# Ancillaries.net
KiCad netlist of a schematic drawn in Altium Designer
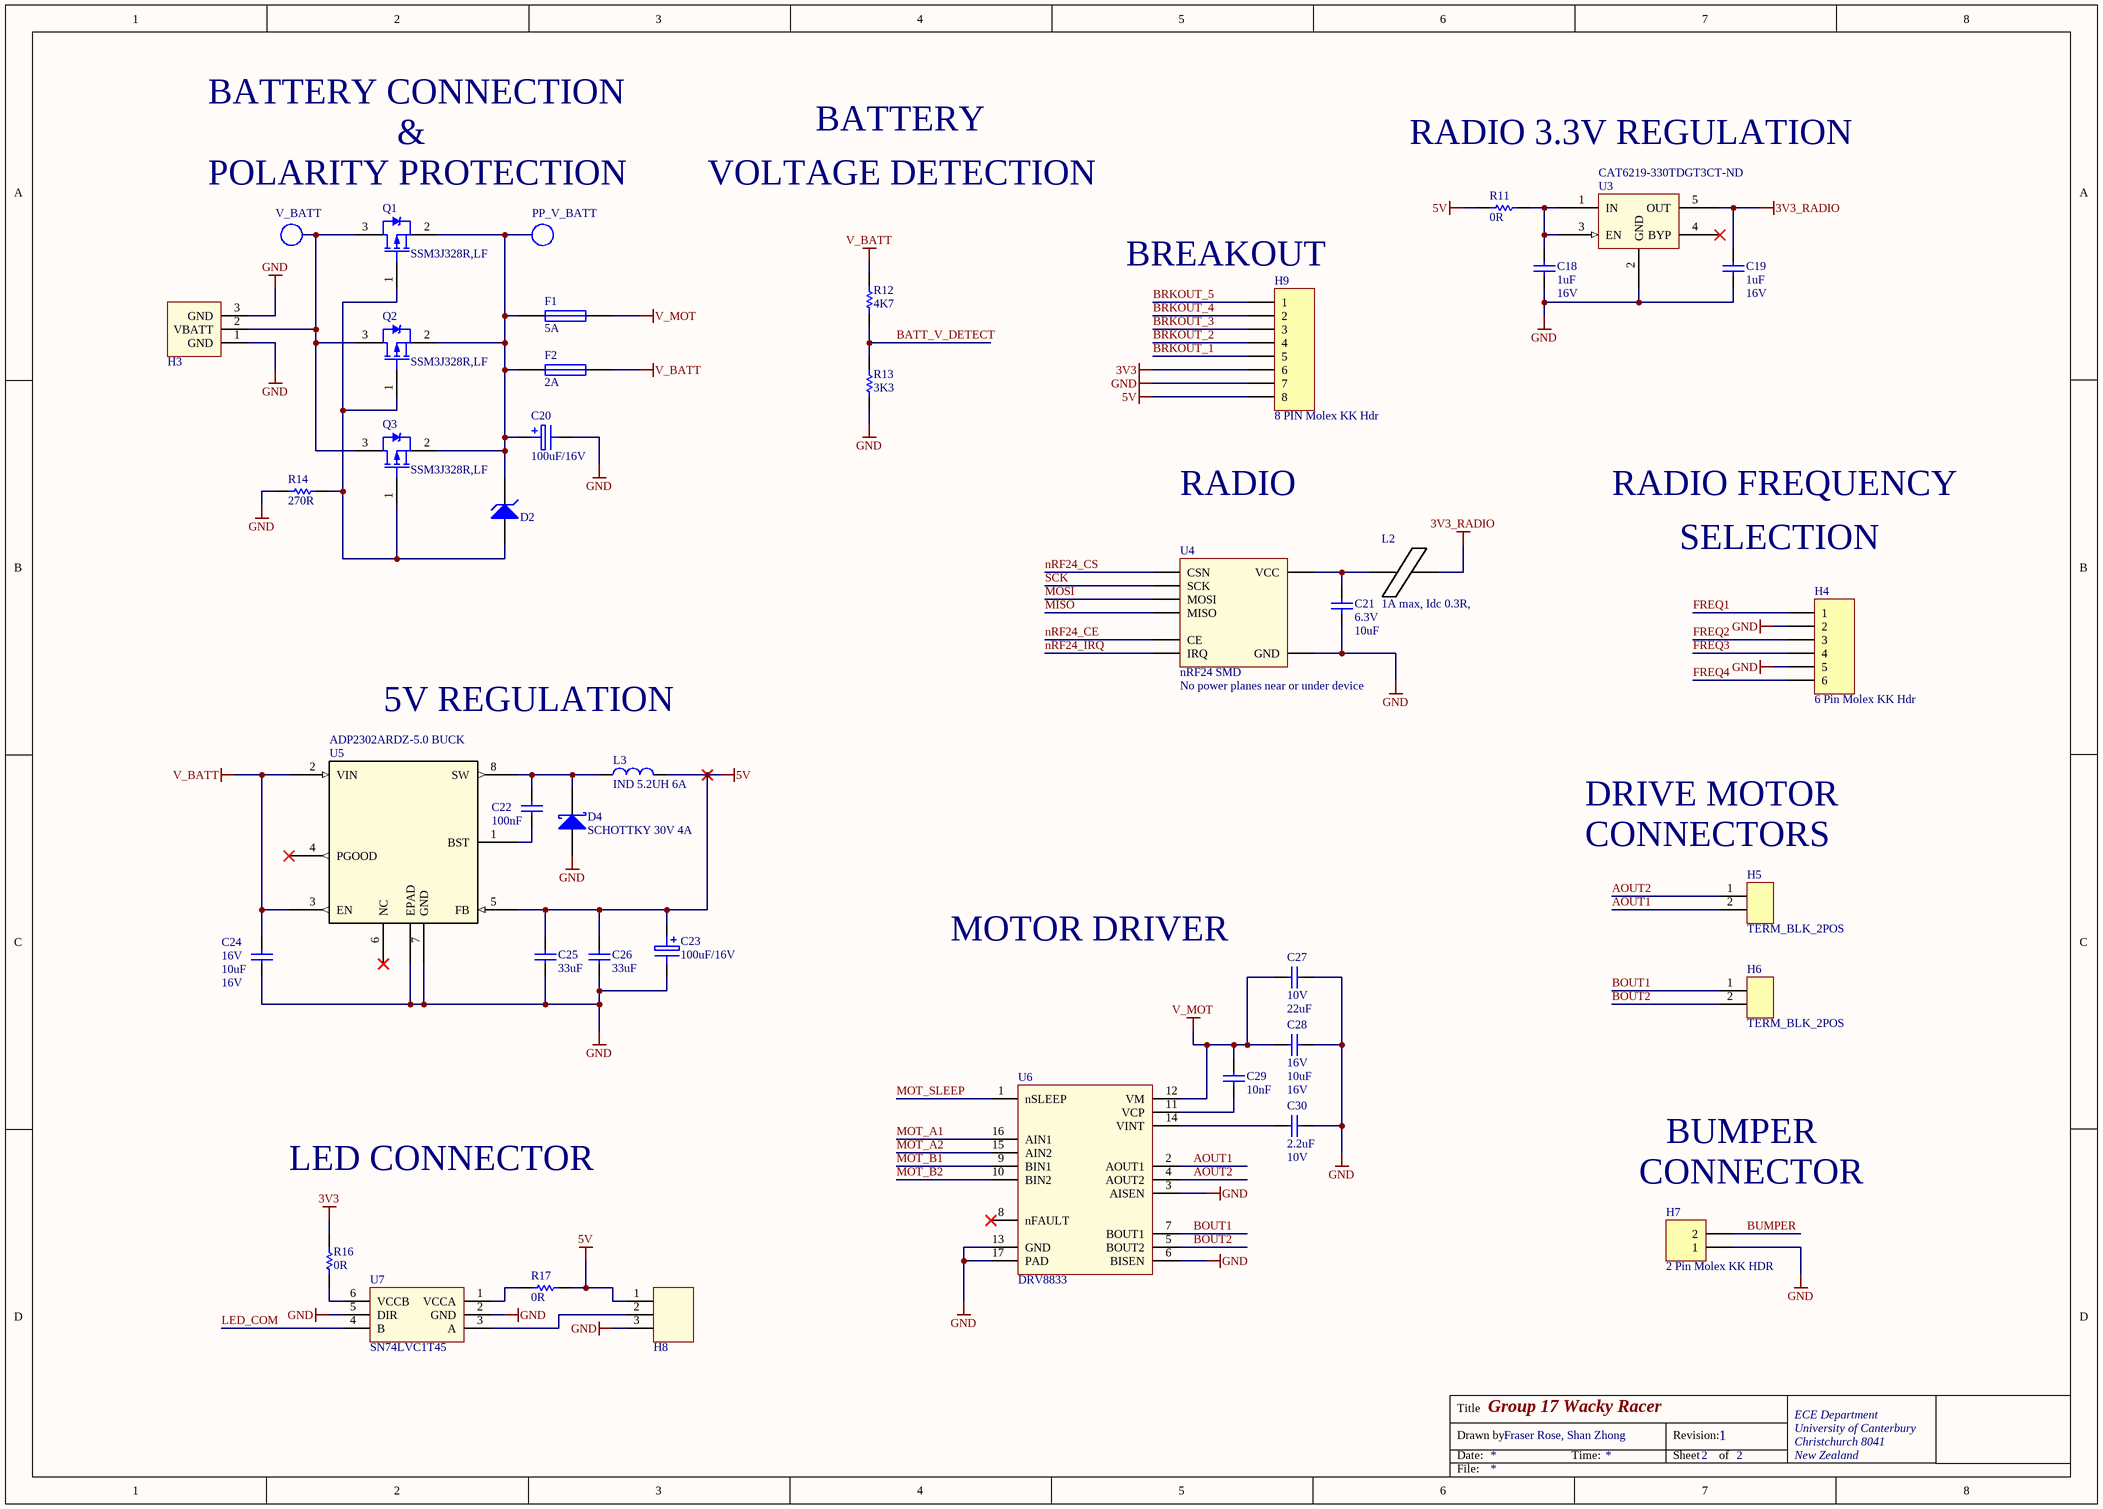
[diagram p0: Ancillaries.SchDoc]

(export (version "E")
  (design (tool "Eeschema 10.0.6"))
  (components
    (comp (ref "1")
      (value "V_BATT")
      (footprint "TP_0603")
      (description "Test Point 1.65X0.9X1.2mm SMD")
      (fields
        (field (name "MANUFACTURER") "TE Connectivity AMP Connectors")
        (field (name "MANUFACTURER PART NUMBER") "1625854-3")
      )
      (libsource (lib "ECE AD19Components_19V1") (part "TP_0603"))
    )
    (comp (ref "2")
      (value "PP_V_BATT")
      (footprint "TP_0603")
      (description "Test Point 1.65X0.9X1.2mm SMD")
      (fields
        (field (name "MANUFACTURER") "TE Connectivity AMP Connectors")
        (field (name "MANUFACTURER PART NUMBER") "1625854-3")
      )
      (libsource (lib "ECE AD19Components_19V1") (part "TP_0603"))
    )
    (comp (ref "C18")
      (value "1uF")
      (footprint "CAPC1608N")
      (description "CAP CER 1uF Y5V -20% +80% 16V 0603")
      (fields (field (name "MAX VOLTAGE") "16V"))
      (libsource (lib "ECE AD19Components_19V1") (part "CC_1uF_0603"))
    )
    (comp (ref "C19")
      (value "1uF")
      (footprint "CAPC1608N")
      (description "CAP CER 1uF Y5V -20% +80% 16V 0603")
      (fields (field (name "MAX VOLTAGE") "16V"))
      (libsource (lib "ECE AD19Components_19V1") (part "CC_1uF_0603"))
    )
    (comp (ref "C20")
      (value "100uF/16V")
      (footprint "NICH-1")
      (description "CAP ALUM 100uF 16V SMD")
      (fields (field (name "MANUFACTURER") "Nichcon"))
      (libsource (lib "ECE AD19Components_19V1") (part "CA_100uF_16V"))
    )
    (comp (ref "C21")
      (value "10uF")
      (footprint "CAPC1608N")
      (description "CAP CER 10UF X5R +-20% 6V3 0603")
      (fields (field (name "VOLTAGE - RATED") "6.3V"))
      (libsource (lib "ECE AD19Components_19V1") (part "CC_10uF_0603"))
    )
    (comp (ref "C22")
      (value "100nF")
      (footprint "CAPC1608N")
      (description "CAP CER 100nF X7R +-10% 50V 0603")
      (libsource (lib "ECE AD19Components_19V1") (part "CC_100nF_0603"))
    )
    (comp (ref "C23")
      (value "100uF/16V")
      (footprint "NICH-1")
      (description "CAP ALUM 100uF 16V SMD")
      (fields (field (name "MANUFACTURER") "Nichcon"))
      (libsource (lib "ECE AD19Components_19V1") (part "CA_100uF_16V"))
    )
    (comp (ref "C24")
      (value "10uF")
      (footprint "CAPC2012N")
      (description "CAP CER 10uF X5R 16V 0805")
      (fields
        (field (name "MANUFACTURER") "Samsung Electro-Mechanics")
        (field (name "MANUFACTURER PART NUMBER") "CL21A106KOQNNWE")
        (field (name "VOLTAGE - RATED") "16V")
        (field (name "MAX VOLTAGE") "16V")
      )
      (libsource (lib "ENCE461AD19_19V2") (part "CC_10uF_16V_0805"))
    )
    (comp (ref "C25")
      (value "33uF")
      (footprint "CAPC2012N")
      (description "CAP CER 33uF X5R 6V3 0805")
      (fields
        (field (name "MANUFACTURER") "TDK Corporation")
        (field (name "MANUFACTURER PART NUMBER") "C2012X5R0J336M125AC")
      )
      (libsource (lib "ENCE461AD19_19V2") (part "CC_33uF_6V3_0805"))
    )
    (comp (ref "C26")
      (value "33uF")
      (footprint "CAPC2012N")
      (description "CAP CER 33uF X5R 6V3 0805")
      (fields
        (field (name "MANUFACTURER") "TDK Corporation")
        (field (name "MANUFACTURER PART NUMBER") "C2012X5R0J336M125AC")
      )
      (libsource (lib "ENCE461AD19_19V2") (part "CC_33uF_6V3_0805"))
    )
    (comp (ref "C27")
      (value "22uF")
      (footprint "CAPC3216N")
      (description "CAP CER 22uF Y5V -20% +80% 10V 1206")
      (fields (field (name "MAX VOLTAGE") "10V"))
      (libsource (lib "ECE AD19Components_19V1") (part "CC_22uF_1206"))
    )
    (comp (ref "C28")
      (value "10uF")
      (footprint "CAPC2012N")
      (description "CAP CER 10uF X5R 16V 0805")
      (fields
        (field (name "MANUFACTURER") "Samsung Electro-Mechanics")
        (field (name "MANUFACTURER PART NUMBER") "CL21A106KOQNNWE")
        (field (name "VOLTAGE - RATED") "16V")
        (field (name "MAX VOLTAGE") "16V")
      )
      (libsource (lib "ENCE461AD19_19V2") (part "CC_10uF_16V_0805"))
    )
    (comp (ref "C29")
      (value "10nF")
      (footprint "CAPC1608N")
      (description "CAP CER 10nF X7R +-10% 50V 0603")
      (libsource (lib "ECE AD19Components_19V1") (part "CC_10nF_0603"))
    )
    (comp (ref "C30")
      (value "2.2uF")
      (footprint "CAPC1608N")
      (description "CAP CER 2.2uF X5R +-20% 10V 0603")
      (fields (field (name "MAX VOLTAGE") "10V"))
      (libsource (lib "ECE AD19Components_19V1") (part "CC_2.2uF_0603"))
    )
    (comp (ref "D2")
      (value "DIODE ZENER 5.6V")
      (footprint "DO-214AA_SCL")
      (description "DIODE ZENER 5.6V 5W DO214AA")
      (fields
        (field (name "MANUFACTURER") "Micro Commercial Co")
        (field (name "MANUFACTURER PART NUMBER") "SMBJ5339B-TP")
      )
      (libsource (lib "ENCE461AD19_19V2") (part "SMBJ5339B-TP"))
    )
    (comp (ref "D4")
      (value "SCHOTTKY 30V 4A")
      (footprint "SMC")
      (description "DIODE SCHOTTKY 30V 4A SMC")
      (fields
        (field (name "MANUFACTURER") "ON Semiconductor")
        (field (name "MANUFACTURER PART NUMBER") "MBRS330T3G")
      )
      (libsource (lib "ENCE461AD19_19V2") (part "MBRS330T3G"))
    )
    (comp (ref "F1")
      (value "5A")
      (footprint "RESC3216N")
      (description "Fuse 5.0A Fast Acting 1206 SMD")
      (fields (field (name "MANUFACTURER PART NUMBER") "C1F5") (field (name "MANUFACTURER") "Bel TRP"))
      (libsource (lib "ECE AD19Components_19V1") (part "FS_Fuse_5.0A"))
    )
    (comp (ref "F2")
      (value "2A")
      (footprint "RESC3216N")
      (description "Fuse 2.0A Very Fast Acting 1206 SMD")
      (fields
        (field (name "MANUFACTURER") "MULTICOMP")
        (field (name "MANUFACTURER PART NUMBER") "MC12CF 002")
      )
      (libsource (lib "ECE AD19Components_19V1") (part "FS_Fuse_2.0A"))
    )
    (comp (ref "H3")
      (value "Battery_HEADER_3pin")
      (footprint "BATT_HEADER_3POS")
      (description "3Pin Header 2.54mm spacing")
      (libsource (lib "ENCE461AD19_19V2") (part "Battery_HEADER_3pin"))
    )
    (comp (ref "H4")
      (value "6 Pin Molex KK Hdr")
      (footprint "MOLEX_KK_6_HDR")
      (description "CONN HEADER 6POS 2.54mm VERT_Thru Hole")
      (libsource (lib "ECE AD19Components_19V1") (part "JA_MOLEX_KK_6POS"))
    )
    (comp (ref "H5")
      (value "TERM_BLK_2POS")
      (footprint "TERM_BLK_2POS")
      (description "2 Position Terminal Block 7.62mm spacing")
      (libsource (lib "ENCE461AD19_19V2") (part "TERM_BLK_2POS"))
    )
    (comp (ref "H6")
      (value "TERM_BLK_2POS")
      (footprint "TERM_BLK_2POS")
      (description "2 Position Terminal Block 7.62mm spacing")
      (libsource (lib "ENCE461AD19_19V2") (part "TERM_BLK_2POS"))
    )
    (comp (ref "H7")
      (value "2 Pin Molex KK HDR")
      (footprint "MOLEX_KK_2_HDR")
      (description "CONN HEADER 2POS 2.54mm VERT_Thru Hole")
      (libsource (lib "ECE AD19Components_19V1") (part "JA_MOLEX_KK_2POS"))
    )
    (comp (ref "H8")
      (value "HEADER_3")
      (footprint "HEADER_3POS")
      (description "3Pin Header 2.54mm spacing")
      (libsource (lib "ENCE461AD19_19V2") (part "HEADER_3"))
    )
    (comp (ref "H9")
      (value "8 PIN Molex KK Hdr")
      (footprint "MOLEX_KK_8_HDR")
      (description "CONN HEADER 8POS 2.54mm VERT_Thru Hole")
      (libsource (lib "ECE AD19Components_19V1") (part "JA_MOLEX_KK_8POS"))
    )
    (comp (ref "L2")
      (value "1A max, Idc 0.3R,")
      (footprint "INDC3216L")
      (description "Ferrite Bead, Rdc 0.3R, Z100MHZ 600R, Imax 1A, SMD 1206")
      (fields
        (field (name "MANUFACTURER") "FAIR-RITE")
        (field (name "MANUFACTURER PART NUMBER") "2512066017Y1")
      )
      (libsource (lib "ECE AD19Components_19V1") (part "IN_Ferrite-Bead"))
    )
    (comp (ref "L3")
      (value "IND 5.2UH 6A")
      (footprint "INDUCTOR5u2")
      (description "FIXED IND 5.2UH 6A 22 MOHM SMD")
      (fields
        (field (name "MANUFACTURER") "Sumida America Components Inc.")
        (field (name "MANUFACTURER PART NUMBER") "CDRH104RNP-5R2NC")
      )
      (libsource (lib "ENCE461AD19_19V2") (part "CDRH104RNP-5R2NC"))
    )
    (comp (ref "Q1")
      (value "SSM3J328R,LF")
      (footprint "SOT23_N")
      (description "MOSFET P-CH 20V 6A SOT23-3")
      (fields
        (field (name "MANUFACTURER") "Toshiba")
        (field (name "MANUFACTURER PART NUMBER") "SSM3J328R,LF")
      )
      (libsource (lib "ECE AD19Components_19V1") (part "TM_SSM3J328R"))
    )
    (comp (ref "Q2")
      (value "SSM3J328R,LF")
      (footprint "SOT23_N")
      (description "MOSFET P-CH 20V 6A SOT23-3")
      (fields
        (field (name "MANUFACTURER") "Toshiba")
        (field (name "MANUFACTURER PART NUMBER") "SSM3J328R,LF")
      )
      (libsource (lib "ECE AD19Components_19V1") (part "TM_SSM3J328R"))
    )
    (comp (ref "Q3")
      (value "SSM3J328R,LF")
      (footprint "SOT23_N")
      (description "MOSFET P-CH 20V 6A SOT23-3")
      (fields
        (field (name "MANUFACTURER") "Toshiba")
        (field (name "MANUFACTURER PART NUMBER") "SSM3J328R,LF")
      )
      (libsource (lib "ECE AD19Components_19V1") (part "TM_SSM3J328R"))
    )
    (comp (ref "R11")
      (value "0R")
      (footprint "RESC1608N")
      (description "RES 0.0 OHM 1/10W 5% 0603 SMD")
      (libsource (lib "ECE AD19Components_19V1") (part "RS_0R0"))
    )
    (comp (ref "R12")
      (value "4K7")
      (footprint "RESC1608N")
      (description "RES 4.7K OHM 1/10W 5% 0603 SMD")
      (libsource (lib "ECE AD19Components_19V1") (part "RS_4K7"))
    )
    (comp (ref "R13")
      (value "3K3")
      (footprint "RESC1608N")
      (description "RES 3.3K OHM 1/10W 5% 0603 SMD")
      (libsource (lib "ECE AD19Components_19V1") (part "RS_3K3"))
    )
    (comp (ref "R14")
      (value "270R")
      (footprint "RESC1608N")
      (description "RES 270 OHM 1/10W 5% 0603 SMD")
      (libsource (lib "ECE AD19Components_19V1") (part "RS_270R"))
    )
    (comp (ref "R16")
      (value "0R")
      (footprint "RESC1608N")
      (description "RES 0.0 OHM 1/10W 5% 0603 SMD")
      (libsource (lib "ECE AD19Components_19V1") (part "RS_0R0"))
    )
    (comp (ref "R17")
      (value "0R")
      (footprint "RESC1608N")
      (description "RES 0.0 OHM 1/10W 5% 0603 SMD")
      (libsource (lib "ECE AD19Components_19V1") (part "RS_0R0"))
    )
    (comp (ref "U3")
      (value "CAT6219-330TDGT3")
      (footprint "SOT95P280X145-5N")
      (description "IC REG LIN 3.3V 500MA TSOT23-5")
      (fields
        (field (name "BASE PART NUMBER") "CAT6219")
        (field (name "SUPPLIER PART NUMBER") "CAT6219-330TDGT3CT-ND")
      )
      (libsource (lib "ENCE461AD19_19V2") (part "SV_CAT6219-330TDGT3"))
    )
    (comp (ref "U4")
      (value "nRF24 SMD")
      (footprint "NRF24")
      (description "nRF24 SMD Module")
      (fields (field (name "WARNING") "No power planes near or under device"))
      (libsource (lib "ENCE461AD19_19V2") (part "NRF24"))
    )
    (comp (ref "U5")
      (value "ADP2302ARDZ-5.0 BUCK")
      (footprint "RD_8_1")
      (description "IC REG BUCK 5V 2A 8SOIC")
      (fields (field (name "MANUFACTURER_PART_NUMBER") "ADP2302ARDZ-5.0-R7"))
      (libsource (lib "ENCE461AD19_19V2") (part "ADP2302ARDZ-5.0-R7"))
    )
    (comp (ref "U6")
      (value "DRV8833")
      (footprint "HTSOP16")
      (description "Dual H-Bridge Motor Driver 1.5A")
      (libsource (lib "ENCE461AD19_19V2") (part "DRV8833"))
    )
    (comp (ref "U7")
      (value "SN74LVC1T45")
      (footprint "SOT23-6_N")
      (description "1.8V - 5V level converter")
      (libsource (lib "ENCE461_extras_2020") (part "SN74LVC1T45"))
    )
  )
  (nets
    (net (code "1") (name "/AOUT1") (class "Default")
      (node (ref "H5") (pin "2") (pintype "passive"))
      (node (ref "U6") (pin "2") (pinfunction "AOUT1_2") (pintype "passive"))
    )
    (net (code "2") (name "/AOUT2") (class "Default")
      (node (ref "H5") (pin "1") (pintype "passive"))
      (node (ref "U6") (pin "4") (pinfunction "AOUT2_4") (pintype "passive"))
    )
    (net (code "3") (name "/BATT_V_DETECT") (class "Default")
      (node (ref "R12") (pin "1") (pinfunction "1_1") (pintype "passive"))
      (node (ref "R13") (pin "2") (pinfunction "2_2") (pintype "passive"))
    )
    (net (code "4") (name "/BOUT1") (class "Default")
      (node (ref "H6") (pin "1") (pintype "passive"))
      (node (ref "U6") (pin "7") (pinfunction "BOUT1_7") (pintype "passive"))
    )
    (net (code "5") (name "/BOUT2") (class "Default")
      (node (ref "H6") (pin "2") (pintype "passive"))
      (node (ref "U6") (pin "5") (pinfunction "BOUT2_5") (pintype "passive"))
    )
    (net (code "6") (name "/BRKOUT_1") (class "Default")
      (node (ref "H9") (pin "5") (pinfunction "5_5") (pintype "passive"))
    )
    (net (code "7") (name "/BRKOUT_2") (class "Default")
      (node (ref "H9") (pin "4") (pinfunction "4_4") (pintype "passive"))
    )
    (net (code "8") (name "/BRKOUT_3") (class "Default")
      (node (ref "H9") (pin "3") (pinfunction "3_3") (pintype "passive"))
    )
    (net (code "9") (name "/BRKOUT_4") (class "Default")
      (node (ref "H9") (pin "2") (pinfunction "2_2") (pintype "passive"))
    )
    (net (code "10") (name "/BRKOUT_5") (class "Default")
      (node (ref "H9") (pin "1") (pinfunction "1_1") (pintype "passive"))
    )
    (net (code "11") (name "/BUMPER") (class "Default")
      (node (ref "H7") (pin "2") (pinfunction "2_2") (pintype "passive"))
    )
    (net (code "12") (name "/FREQ1") (class "Default")
      (node (ref "H4") (pin "1") (pinfunction "1_1") (pintype "passive"))
    )
    (net (code "13") (name "/FREQ2") (class "Default")
      (node (ref "H4") (pin "3") (pinfunction "3_3") (pintype "passive"))
    )
    (net (code "14") (name "/FREQ3") (class "Default")
      (node (ref "H4") (pin "4") (pinfunction "4_4") (pintype "passive"))
    )
    (net (code "15") (name "/FREQ4") (class "Default")
      (node (ref "H4") (pin "6") (pinfunction "6_6") (pintype "passive"))
    )
    (net (code "16") (name "/LED_COM") (class "Default")
      (node (ref "U7") (pin "4") (pinfunction "B_4") (pintype "passive"))
    )
    (net (code "17") (name "/MISO") (class "Default")
      (node (ref "U4") (pin "7") (pinfunction "MISO_7") (pintype "passive"))
    )
    (net (code "18") (name "/MOSI") (class "Default")
      (node (ref "U4") (pin "6") (pinfunction "MOSI_6") (pintype "passive"))
    )
    (net (code "19") (name "/MOT_A1") (class "Default")
      (node (ref "U6") (pin "16") (pinfunction "AIN1_16") (pintype "passive"))
    )
    (net (code "20") (name "/MOT_A2") (class "Default")
      (node (ref "U6") (pin "15") (pinfunction "AIN2_15") (pintype "passive"))
    )
    (net (code "21") (name "/MOT_B1") (class "Default")
      (node (ref "U6") (pin "9") (pinfunction "BIN1_9") (pintype "passive"))
    )
    (net (code "22") (name "/MOT_B2") (class "Default")
      (node (ref "U6") (pin "10") (pinfunction "BIN2_10") (pintype "passive"))
    )
    (net (code "23") (name "/MOT_SLEEP") (class "Default")
      (node (ref "U6") (pin "1") (pinfunction "nSLEEP_1") (pintype "passive"))
    )
    (net (code "24") (name "/SCK") (class "Default")
      (node (ref "U4") (pin "5") (pinfunction "SCK_5") (pintype "passive"))
    )
    (net (code "25") (name "/nRF24_CE") (class "Default")
      (node (ref "U4") (pin "3") (pinfunction "CE_3") (pintype "passive"))
    )
    (net (code "26") (name "/nRF24_CS") (class "Default")
      (node (ref "U4") (pin "4") (pinfunction "CSN_4") (pintype "passive"))
    )
    (net (code "27") (name "/nRF24_IRQ") (class "Default")
      (node (ref "U4") (pin "8") (pinfunction "IRQ_8") (pintype "passive"))
    )
    (net (code "28") (name "3V3") (class "Default")
      (node (ref "H9") (pin "6") (pinfunction "6_6") (pintype "passive"))
      (node (ref "R16") (pin "2") (pinfunction "2_2") (pintype "passive"))
    )
    (net (code "29") (name "3V3_RADIO") (class "Default")
      (node (ref "C19") (pin "2") (pinfunction "2_2") (pintype "passive"))
      (node (ref "L2") (pin "2") (pinfunction "2_2") (pintype "passive"))
      (node (ref "U3") (pin "5") (pinfunction "OUT_5") (pintype "power_in"))
    )
    (net (code "30") (name "5V") (class "Default")
      (node (ref "C23") (pin "2") (pintype "passive"))
      (node (ref "C25") (pin "2") (pinfunction "2_2") (pintype "passive"))
      (node (ref "C26") (pin "2") (pinfunction "2_2") (pintype "passive"))
      (node (ref "H8") (pin "1") (pintype "passive"))
      (node (ref "H9") (pin "8") (pinfunction "8_8") (pintype "passive"))
      (node (ref "L3") (pin "2") (pintype "passive"))
      (node (ref "R11") (pin "2") (pinfunction "2_2") (pintype "passive"))
      (node (ref "R17") (pin "2") (pinfunction "2_2") (pintype "passive"))
      (node (ref "U5") (pin "5") (pinfunction "FB_5") (pintype "input"))
    )
    (net (code "31") (name "GND") (class "Default")
      (node (ref "C18") (pin "1") (pinfunction "1_1") (pintype "passive"))
      (node (ref "C19") (pin "1") (pinfunction "1_1") (pintype "passive"))
      (node (ref "C20") (pin "1") (pintype "passive"))
      (node (ref "C21") (pin "1") (pinfunction "1_1") (pintype "passive"))
      (node (ref "C23") (pin "1") (pintype "passive"))
      (node (ref "C24") (pin "1") (pinfunction "1_1") (pintype "passive"))
      (node (ref "C25") (pin "1") (pinfunction "1_1") (pintype "passive"))
      (node (ref "C26") (pin "1") (pinfunction "1_1") (pintype "passive"))
      (node (ref "C27") (pin "2") (pinfunction "2_2") (pintype "passive"))
      (node (ref "C28") (pin "1") (pinfunction "1_1") (pintype "passive"))
      (node (ref "C30") (pin "1") (pinfunction "1_1") (pintype "passive"))
      (node (ref "D4") (pin "1") (pinfunction "A_1") (pintype "passive"))
      (node (ref "H3") (pin "1") (pinfunction "GND_1") (pintype "passive"))
      (node (ref "H3") (pin "3") (pinfunction "GND_3") (pintype "passive"))
      (node (ref "H4") (pin "2") (pinfunction "2_2") (pintype "passive"))
      (node (ref "H4") (pin "5") (pinfunction "5_5") (pintype "passive"))
      (node (ref "H7") (pin "1") (pinfunction "1_1") (pintype "passive"))
      (node (ref "H8") (pin "3") (pintype "passive"))
      (node (ref "H9") (pin "7") (pinfunction "7_7") (pintype "passive"))
      (node (ref "R13") (pin "1") (pinfunction "1_1") (pintype "passive"))
      (node (ref "R14") (pin "2") (pinfunction "2_2") (pintype "passive"))
      (node (ref "U3") (pin "2") (pinfunction "GND_2") (pintype "power_in"))
      (node (ref "U4") (pin "2") (pinfunction "GND_2") (pintype "passive"))
      (node (ref "U5") (pin "7") (pinfunction "GND_7") (pintype "power_in"))
      (node (ref "U5") (pin "EPAD") (pinfunction "EPAD_EPAD") (pintype "passive"))
      (node (ref "U6") (pin "13") (pinfunction "GND_13") (pintype "passive"))
      (node (ref "U6") (pin "17") (pinfunction "PAD_17") (pintype "passive"))
      (node (ref "U6") (pin "3") (pinfunction "AISEN_3") (pintype "passive"))
      (node (ref "U6") (pin "6") (pinfunction "BISEN_6") (pintype "passive"))
      (node (ref "U7") (pin "2") (pinfunction "GND_2") (pintype "passive"))
      (node (ref "U7") (pin "5") (pinfunction "DIR_5") (pintype "passive"))
    )
    (net (code "32") (name "Net-(1-TP)") (class "Default")
      (node (ref "1") (pin "1") (pinfunction "TP_1") (pintype "passive"))
      (node (ref "H3") (pin "2") (pinfunction "VBATT_2") (pintype "passive"))
      (node (ref "Q1") (pin "3") (pinfunction "3_3") (pintype "passive"))
      (node (ref "Q2") (pin "3") (pinfunction "3_3") (pintype "passive"))
      (node (ref "Q3") (pin "3") (pinfunction "3_3") (pintype "passive"))
    )
    (net (code "33") (name "Net-(2-TP)") (class "Default")
      (node (ref "2") (pin "1") (pinfunction "TP_1") (pintype "passive"))
      (node (ref "C20") (pin "2") (pintype "passive"))
      (node (ref "D2") (pin "1") (pinfunction "K_1") (pintype "passive"))
      (node (ref "F1") (pin "1") (pinfunction "1_1") (pintype "passive"))
      (node (ref "F2") (pin "1") (pinfunction "1_1") (pintype "passive"))
      (node (ref "Q1") (pin "2") (pinfunction "2_2") (pintype "passive"))
      (node (ref "Q2") (pin "2") (pinfunction "2_2") (pintype "passive"))
      (node (ref "Q3") (pin "2") (pinfunction "2_2") (pintype "passive"))
    )
    (net (code "34") (name "Net-(D2-A)") (class "Default")
      (node (ref "D2") (pin "2") (pinfunction "A_2") (pintype "passive"))
      (node (ref "Q1") (pin "1") (pinfunction "1_1") (pintype "passive"))
      (node (ref "Q2") (pin "1") (pinfunction "1_1") (pintype "passive"))
      (node (ref "Q3") (pin "1") (pinfunction "1_1") (pintype "passive"))
      (node (ref "R14") (pin "1") (pinfunction "1_1") (pintype "passive"))
    )
    (net (code "35") (name "Net-(D4-K)") (class "Default")
      (node (ref "C22") (pin "2") (pinfunction "2_2") (pintype "passive"))
      (node (ref "D4") (pin "2") (pinfunction "K_2") (pintype "passive"))
      (node (ref "L3") (pin "1") (pintype "passive"))
      (node (ref "U5") (pin "8") (pinfunction "SW_8") (pintype "output"))
    )
    (net (code "36") (name "Net-(U3-EN)") (class "Default")
      (node (ref "C18") (pin "2") (pinfunction "2_2") (pintype "passive"))
      (node (ref "R11") (pin "1") (pinfunction "1_1") (pintype "passive"))
      (node (ref "U3") (pin "1") (pinfunction "IN_1") (pintype "power_in"))
      (node (ref "U3") (pin "3") (pinfunction "EN_3") (pintype "input"))
    )
    (net (code "37") (name "Net-(U4-VCC)") (class "Default")
      (node (ref "C21") (pin "2") (pinfunction "2_2") (pintype "passive"))
      (node (ref "L2") (pin "1") (pinfunction "1_1") (pintype "passive"))
      (node (ref "U4") (pin "1") (pinfunction "VCC_1") (pintype "passive"))
    )
    (net (code "38") (name "Net-(U5-BST)") (class "Default")
      (node (ref "C22") (pin "1") (pinfunction "1_1") (pintype "passive"))
      (node (ref "U5") (pin "1") (pinfunction "BST_1") (pintype "passive"))
    )
    (net (code "39") (name "Net-(U6-VCP)") (class "Default")
      (node (ref "C29") (pin "1") (pinfunction "1_1") (pintype "passive"))
      (node (ref "U6") (pin "11") (pinfunction "VCP_11") (pintype "passive"))
    )
    (net (code "40") (name "Net-(U6-VINT)") (class "Default")
      (node (ref "C30") (pin "2") (pinfunction "2_2") (pintype "passive"))
      (node (ref "U6") (pin "14") (pinfunction "VINT_14") (pintype "passive"))
    )
    (net (code "41") (name "Net-(U7-A)") (class "Default")
      (node (ref "H8") (pin "2") (pintype "passive"))
      (node (ref "U7") (pin "3") (pinfunction "A_3") (pintype "passive"))
    )
    (net (code "42") (name "Net-(U7-VCCA)") (class "Default")
      (node (ref "R17") (pin "1") (pinfunction "1_1") (pintype "passive"))
      (node (ref "U7") (pin "1") (pinfunction "VCCA_1") (pintype "passive"))
    )
    (net (code "43") (name "Net-(U7-VCCB)") (class "Default")
      (node (ref "R16") (pin "1") (pinfunction "1_1") (pintype "passive"))
      (node (ref "U7") (pin "6") (pinfunction "VCCB_6") (pintype "passive"))
    )
    (net (code "44") (name "V_BATT") (class "Default")
      (node (ref "C24") (pin "2") (pinfunction "2_2") (pintype "passive"))
      (node (ref "F2") (pin "2") (pinfunction "2_2") (pintype "passive"))
      (node (ref "R12") (pin "2") (pinfunction "2_2") (pintype "passive"))
      (node (ref "U5") (pin "2") (pinfunction "VIN_2") (pintype "input"))
      (node (ref "U5") (pin "3") (pinfunction "EN_3") (pintype "output"))
    )
    (net (code "45") (name "V_MOT") (class "Default")
      (node (ref "C27") (pin "1") (pinfunction "1_1") (pintype "passive"))
      (node (ref "C28") (pin "2") (pinfunction "2_2") (pintype "passive"))
      (node (ref "C29") (pin "2") (pinfunction "2_2") (pintype "passive"))
      (node (ref "F1") (pin "2") (pinfunction "2_2") (pintype "passive"))
      (node (ref "U6") (pin "12") (pinfunction "VM_12") (pintype "passive"))
    )
    (net (code "46") (name "unconnected-(U3-BYP-Pad4)") (class "Default")
      (node (ref "U3") (pin "4") (pinfunction "BYP_4") (pintype "passive+no_connect"))
    )
    (net (code "47") (name "unconnected-(U5-NC-Pad6)") (class "Default")
      (node (ref "U5") (pin "6") (pinfunction "NC_6") (pintype "passive+no_connect"))
    )
    (net (code "48") (name "unconnected-(U5-PGOOD-Pad4)") (class "Default")
      (node (ref "U5") (pin "4") (pinfunction "PGOOD_4") (pintype "output+no_connect"))
    )
    (net (code "49") (name "unconnected-(U6-nFAULT-Pad8)") (class "Default")
      (node (ref "U6") (pin "8") (pinfunction "nFAULT_8") (pintype "passive+no_connect"))
    )
  )
)
